# max232.net
KiCad netlist of a schematic drawn in EAGLE
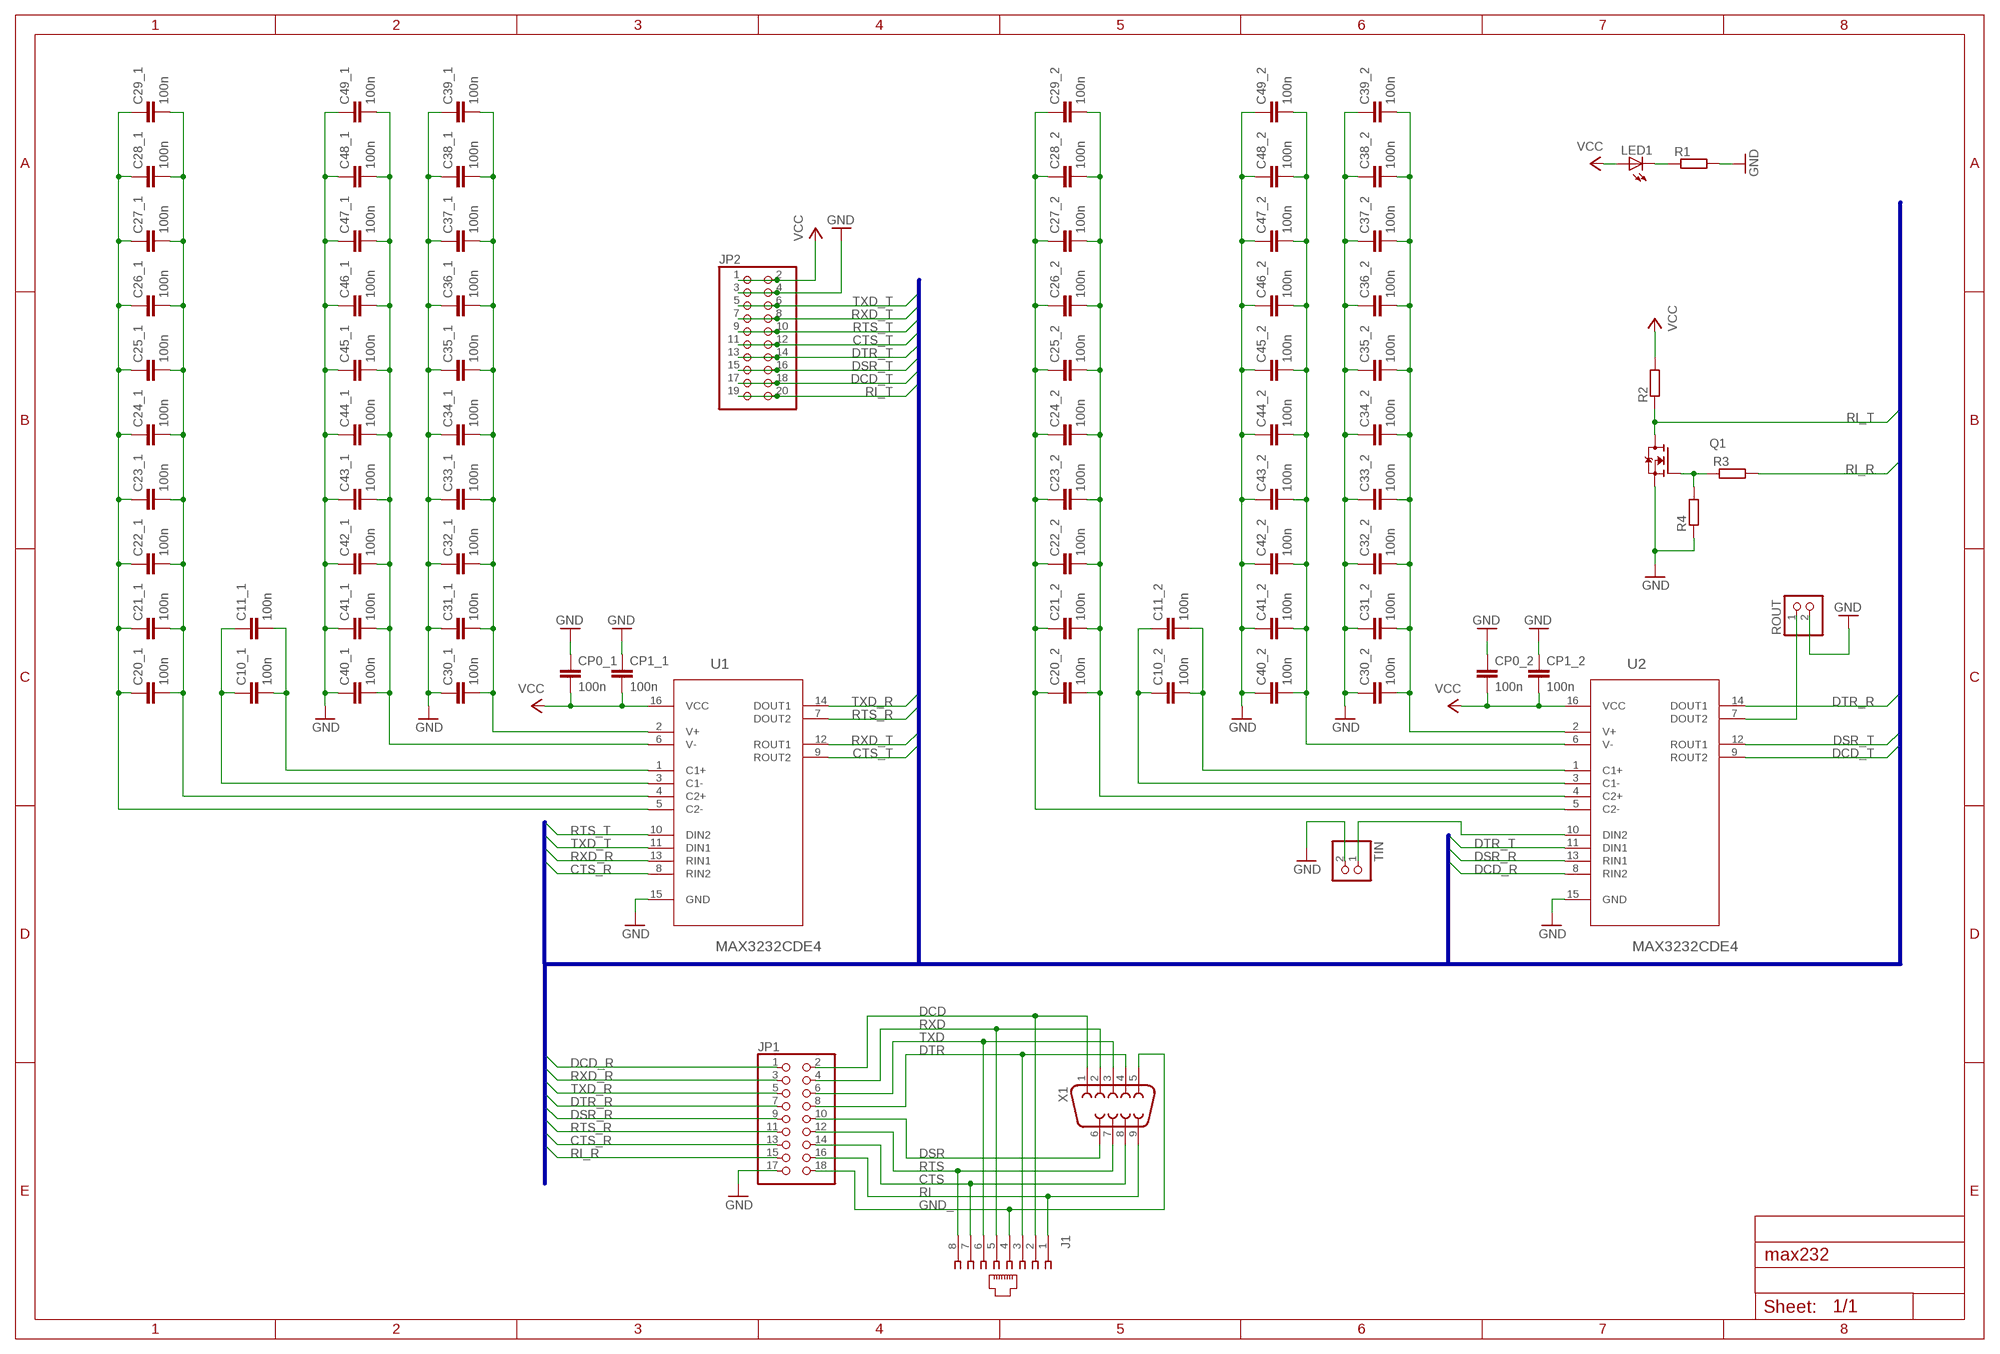
[diagram p0: schematic, sheet 1]

(export (version "E")
  (design (tool "Eeschema 10.0.6"))
  (components
    (comp (ref "C10_1")
      (value "100n")
      (footprint "eagle-import:C0402")
      (libsource (lib "eagle-import") (part "C-EUC0402"))
    )
    (comp (ref "C10_2")
      (value "100n")
      (footprint "eagle-import:C0402")
      (libsource (lib "eagle-import") (part "C-EUC0402"))
    )
    (comp (ref "C11_1")
      (value "100n")
      (footprint "eagle-import:C0402")
      (libsource (lib "eagle-import") (part "C-EUC0402"))
    )
    (comp (ref "C11_2")
      (value "100n")
      (footprint "eagle-import:C0402")
      (libsource (lib "eagle-import") (part "C-EUC0402"))
    )
    (comp (ref "C20_1")
      (value "100n")
      (footprint "eagle-import:C0402")
      (libsource (lib "eagle-import") (part "C-EUC0402"))
    )
    (comp (ref "C20_2")
      (value "100n")
      (footprint "eagle-import:C0402")
      (libsource (lib "eagle-import") (part "C-EUC0402"))
    )
    (comp (ref "C21_1")
      (value "100n")
      (footprint "eagle-import:C0402")
      (libsource (lib "eagle-import") (part "C-EUC0402"))
    )
    (comp (ref "C21_2")
      (value "100n")
      (footprint "eagle-import:C0402")
      (libsource (lib "eagle-import") (part "C-EUC0402"))
    )
    (comp (ref "C22_1")
      (value "100n")
      (footprint "eagle-import:C0402")
      (libsource (lib "eagle-import") (part "C-EUC0402"))
    )
    (comp (ref "C22_2")
      (value "100n")
      (footprint "eagle-import:C0402")
      (libsource (lib "eagle-import") (part "C-EUC0402"))
    )
    (comp (ref "C23_1")
      (value "100n")
      (footprint "eagle-import:C0402")
      (libsource (lib "eagle-import") (part "C-EUC0402"))
    )
    (comp (ref "C23_2")
      (value "100n")
      (footprint "eagle-import:C0402")
      (libsource (lib "eagle-import") (part "C-EUC0402"))
    )
    (comp (ref "C24_1")
      (value "100n")
      (footprint "eagle-import:C0402")
      (libsource (lib "eagle-import") (part "C-EUC0402"))
    )
    (comp (ref "C24_2")
      (value "100n")
      (footprint "eagle-import:C0402")
      (libsource (lib "eagle-import") (part "C-EUC0402"))
    )
    (comp (ref "C25_1")
      (value "100n")
      (footprint "eagle-import:C0402")
      (libsource (lib "eagle-import") (part "C-EUC0402"))
    )
    (comp (ref "C25_2")
      (value "100n")
      (footprint "eagle-import:C0402")
      (libsource (lib "eagle-import") (part "C-EUC0402"))
    )
    (comp (ref "C26_1")
      (value "100n")
      (footprint "eagle-import:C0402")
      (libsource (lib "eagle-import") (part "C-EUC0402"))
    )
    (comp (ref "C26_2")
      (value "100n")
      (footprint "eagle-import:C0402")
      (libsource (lib "eagle-import") (part "C-EUC0402"))
    )
    (comp (ref "C27_1")
      (value "100n")
      (footprint "eagle-import:C0402")
      (libsource (lib "eagle-import") (part "C-EUC0402"))
    )
    (comp (ref "C27_2")
      (value "100n")
      (footprint "eagle-import:C0402")
      (libsource (lib "eagle-import") (part "C-EUC0402"))
    )
    (comp (ref "C28_1")
      (value "100n")
      (footprint "eagle-import:C0402")
      (libsource (lib "eagle-import") (part "C-EUC0402"))
    )
    (comp (ref "C28_2")
      (value "100n")
      (footprint "eagle-import:C0402")
      (libsource (lib "eagle-import") (part "C-EUC0402"))
    )
    (comp (ref "C29_1")
      (value "100n")
      (footprint "eagle-import:C0402")
      (libsource (lib "eagle-import") (part "C-EUC0402"))
    )
    (comp (ref "C29_2")
      (value "100n")
      (footprint "eagle-import:C0402")
      (libsource (lib "eagle-import") (part "C-EUC0402"))
    )
    (comp (ref "C30_1")
      (value "100n")
      (footprint "eagle-import:C0402")
      (libsource (lib "eagle-import") (part "C-EUC0402"))
    )
    (comp (ref "C30_2")
      (value "100n")
      (footprint "eagle-import:C0402")
      (libsource (lib "eagle-import") (part "C-EUC0402"))
    )
    (comp (ref "C31_1")
      (value "100n")
      (footprint "eagle-import:C0402")
      (libsource (lib "eagle-import") (part "C-EUC0402"))
    )
    (comp (ref "C31_2")
      (value "100n")
      (footprint "eagle-import:C0402")
      (libsource (lib "eagle-import") (part "C-EUC0402"))
    )
    (comp (ref "C32_1")
      (value "100n")
      (footprint "eagle-import:C0402")
      (libsource (lib "eagle-import") (part "C-EUC0402"))
    )
    (comp (ref "C32_2")
      (value "100n")
      (footprint "eagle-import:C0402")
      (libsource (lib "eagle-import") (part "C-EUC0402"))
    )
    (comp (ref "C33_1")
      (value "100n")
      (footprint "eagle-import:C0402")
      (libsource (lib "eagle-import") (part "C-EUC0402"))
    )
    (comp (ref "C33_2")
      (value "100n")
      (footprint "eagle-import:C0402")
      (libsource (lib "eagle-import") (part "C-EUC0402"))
    )
    (comp (ref "C34_1")
      (value "100n")
      (footprint "eagle-import:C0402")
      (libsource (lib "eagle-import") (part "C-EUC0402"))
    )
    (comp (ref "C34_2")
      (value "100n")
      (footprint "eagle-import:C0402")
      (libsource (lib "eagle-import") (part "C-EUC0402"))
    )
    (comp (ref "C35_1")
      (value "100n")
      (footprint "eagle-import:C0402")
      (libsource (lib "eagle-import") (part "C-EUC0402"))
    )
    (comp (ref "C35_2")
      (value "100n")
      (footprint "eagle-import:C0402")
      (libsource (lib "eagle-import") (part "C-EUC0402"))
    )
    (comp (ref "C36_1")
      (value "100n")
      (footprint "eagle-import:C0402")
      (libsource (lib "eagle-import") (part "C-EUC0402"))
    )
    (comp (ref "C36_2")
      (value "100n")
      (footprint "eagle-import:C0402")
      (libsource (lib "eagle-import") (part "C-EUC0402"))
    )
    (comp (ref "C37_1")
      (value "100n")
      (footprint "eagle-import:C0402")
      (libsource (lib "eagle-import") (part "C-EUC0402"))
    )
    (comp (ref "C37_2")
      (value "100n")
      (footprint "eagle-import:C0402")
      (libsource (lib "eagle-import") (part "C-EUC0402"))
    )
    (comp (ref "C38_1")
      (value "100n")
      (footprint "eagle-import:C0402")
      (libsource (lib "eagle-import") (part "C-EUC0402"))
    )
    (comp (ref "C38_2")
      (value "100n")
      (footprint "eagle-import:C0402")
      (libsource (lib "eagle-import") (part "C-EUC0402"))
    )
    (comp (ref "C39_1")
      (value "100n")
      (footprint "eagle-import:C0402")
      (libsource (lib "eagle-import") (part "C-EUC0402"))
    )
    (comp (ref "C39_2")
      (value "100n")
      (footprint "eagle-import:C0402")
      (libsource (lib "eagle-import") (part "C-EUC0402"))
    )
    (comp (ref "C40_1")
      (value "100n")
      (footprint "eagle-import:C0402")
      (libsource (lib "eagle-import") (part "C-EUC0402"))
    )
    (comp (ref "C40_2")
      (value "100n")
      (footprint "eagle-import:C0402")
      (libsource (lib "eagle-import") (part "C-EUC0402"))
    )
    (comp (ref "C41_1")
      (value "100n")
      (footprint "eagle-import:C0402")
      (libsource (lib "eagle-import") (part "C-EUC0402"))
    )
    (comp (ref "C41_2")
      (value "100n")
      (footprint "eagle-import:C0402")
      (libsource (lib "eagle-import") (part "C-EUC0402"))
    )
    (comp (ref "C42_1")
      (value "100n")
      (footprint "eagle-import:C0402")
      (libsource (lib "eagle-import") (part "C-EUC0402"))
    )
    (comp (ref "C42_2")
      (value "100n")
      (footprint "eagle-import:C0402")
      (libsource (lib "eagle-import") (part "C-EUC0402"))
    )
    (comp (ref "C43_1")
      (value "100n")
      (footprint "eagle-import:C0402")
      (libsource (lib "eagle-import") (part "C-EUC0402"))
    )
    (comp (ref "C43_2")
      (value "100n")
      (footprint "eagle-import:C0402")
      (libsource (lib "eagle-import") (part "C-EUC0402"))
    )
    (comp (ref "C44_1")
      (value "100n")
      (footprint "eagle-import:C0402")
      (libsource (lib "eagle-import") (part "C-EUC0402"))
    )
    (comp (ref "C44_2")
      (value "100n")
      (footprint "eagle-import:C0402")
      (libsource (lib "eagle-import") (part "C-EUC0402"))
    )
    (comp (ref "C45_1")
      (value "100n")
      (footprint "eagle-import:C0402")
      (libsource (lib "eagle-import") (part "C-EUC0402"))
    )
    (comp (ref "C45_2")
      (value "100n")
      (footprint "eagle-import:C0402")
      (libsource (lib "eagle-import") (part "C-EUC0402"))
    )
    (comp (ref "C46_1")
      (value "100n")
      (footprint "eagle-import:C0402")
      (libsource (lib "eagle-import") (part "C-EUC0402"))
    )
    (comp (ref "C46_2")
      (value "100n")
      (footprint "eagle-import:C0402")
      (libsource (lib "eagle-import") (part "C-EUC0402"))
    )
    (comp (ref "C47_1")
      (value "100n")
      (footprint "eagle-import:C0402")
      (libsource (lib "eagle-import") (part "C-EUC0402"))
    )
    (comp (ref "C47_2")
      (value "100n")
      (footprint "eagle-import:C0402")
      (libsource (lib "eagle-import") (part "C-EUC0402"))
    )
    (comp (ref "C48_1")
      (value "100n")
      (footprint "eagle-import:C0402")
      (libsource (lib "eagle-import") (part "C-EUC0402"))
    )
    (comp (ref "C48_2")
      (value "100n")
      (footprint "eagle-import:C0402")
      (libsource (lib "eagle-import") (part "C-EUC0402"))
    )
    (comp (ref "C49_1")
      (value "100n")
      (footprint "eagle-import:C0402")
      (libsource (lib "eagle-import") (part "C-EUC0402"))
    )
    (comp (ref "C49_2")
      (value "100n")
      (footprint "eagle-import:C0402")
      (libsource (lib "eagle-import") (part "C-EUC0402"))
    )
    (comp (ref "CP0_1")
      (value "100n")
      (footprint "eagle-import:C0402")
      (libsource (lib "eagle-import") (part "C-EUC0402"))
    )
    (comp (ref "CP0_2")
      (value "100n")
      (footprint "eagle-import:C0402")
      (libsource (lib "eagle-import") (part "C-EUC0402"))
    )
    (comp (ref "CP1_1")
      (value "100n")
      (footprint "eagle-import:C0402")
      (libsource (lib "eagle-import") (part "C-EUC0402"))
    )
    (comp (ref "CP1_2")
      (value "100n")
      (footprint "eagle-import:C0402")
      (libsource (lib "eagle-import") (part "C-EUC0402"))
    )
    (comp (ref "J1")
      (value "215877-4")
      (footprint "eagle-import:215877-4")
      (libsource (lib "eagle-import") (part "215877-4"))
    )
    (comp (ref "JP1")
      (value "PINHD-2X9")
      (footprint "eagle-import:2X09")
      (libsource (lib "eagle-import") (part "PINHD-2X9"))
    )
    (comp (ref "JP2")
      (value "PINHD-2X10/90")
      (footprint "eagle-import:2X10_90")
      (libsource (lib "eagle-import") (part "PINHD-2X10/90"))
    )
    (comp (ref "LED1")
      (value "LEDCHIP-LED0603")
      (footprint "eagle-import:CHIP-LED0603")
      (libsource (lib "eagle-import") (part "LEDCHIP-LED0603"))
    )
    (comp (ref "Q1")
      (value "N-MOSFET-SOT23-GSD")
      (footprint "eagle-import:SOT23")
      (libsource (lib "eagle-import") (part "N-MOSFET-SOT23-GSD"))
    )
    (comp (ref "R1")
      (value "R-EU_R0603")
      (footprint "eagle-import:R0603")
      (libsource (lib "eagle-import") (part "R-EU_R0603"))
    )
    (comp (ref "R2")
      (value "R-EU_R0603")
      (footprint "eagle-import:R0603")
      (libsource (lib "eagle-import") (part "R-EU_R0603"))
    )
    (comp (ref "R3")
      (value "R-EU_R0603")
      (footprint "eagle-import:R0603")
      (libsource (lib "eagle-import") (part "R-EU_R0603"))
    )
    (comp (ref "R4")
      (value "R-EU_R0603")
      (footprint "eagle-import:R0603")
      (libsource (lib "eagle-import") (part "R-EU_R0603"))
    )
    (comp (ref "ROUT")
      (value "PINHD-1X2")
      (footprint "eagle-import:1X02")
      (libsource (lib "eagle-import") (part "PINHD-1X2"))
    )
    (comp (ref "TIN")
      (value "PINHD-1X2")
      (footprint "eagle-import:1X02")
      (libsource (lib "eagle-import") (part "PINHD-1X2"))
    )
    (comp (ref "U1")
      (value "MAX3232CDE4")
      (footprint "eagle-import:SOIC127P600X175-16N")
      (libsource (lib "eagle-import") (part "MAX3232CDE4"))
    )
    (comp (ref "U2")
      (value "MAX3232CDE4")
      (footprint "eagle-import:SOIC127P600X175-16N")
      (libsource (lib "eagle-import") (part "MAX3232CDE4"))
    )
    (comp (ref "X1")
      (value "F09HP")
      (footprint "eagle-import:F09HP")
      (libsource (lib "eagle-import") (part "F09HP"))
    )
  )
  (nets
    (net (code "1") (name "/CTS") (class "Default")
      (node (ref "J1") (pin "7") (pinfunction "7_7") (pintype "passive"))
      (node (ref "JP1") (pin "14") (pinfunction "14_14") (pintype "passive"))
      (node (ref "X1") (pin "8") (pinfunction "8_8") (pintype "passive"))
    )
    (net (code "2") (name "/CTS_R") (class "Default")
      (node (ref "JP1") (pin "13") (pinfunction "13_13") (pintype "passive"))
      (node (ref "U1") (pin "8") (pinfunction "RIN2_8") (pintype "input"))
    )
    (net (code "3") (name "/CTS_T") (class "Default")
      (node (ref "JP2") (pin "11") (pinfunction "11_11") (pintype "passive"))
      (node (ref "JP2") (pin "12") (pinfunction "12_12") (pintype "passive"))
      (node (ref "U1") (pin "9") (pinfunction "ROUT2_9") (pintype "output"))
    )
    (net (code "4") (name "/DCD") (class "Default")
      (node (ref "J1") (pin "2") (pinfunction "2_2") (pintype "passive"))
      (node (ref "JP1") (pin "2") (pinfunction "2_2") (pintype "passive"))
      (node (ref "X1") (pin "1") (pinfunction "1_1") (pintype "passive"))
    )
    (net (code "5") (name "/DCD_R") (class "Default")
      (node (ref "JP1") (pin "1") (pinfunction "1_1") (pintype "passive"))
      (node (ref "U2") (pin "8") (pinfunction "RIN2_8") (pintype "input"))
    )
    (net (code "6") (name "/DCD_T") (class "Default")
      (node (ref "JP2") (pin "17") (pinfunction "17_17") (pintype "passive"))
      (node (ref "JP2") (pin "18") (pinfunction "18_18") (pintype "passive"))
      (node (ref "U2") (pin "9") (pinfunction "ROUT2_9") (pintype "output"))
    )
    (net (code "7") (name "/DSR") (class "Default")
      (node (ref "JP1") (pin "10") (pinfunction "10_10") (pintype "passive"))
      (node (ref "X1") (pin "6") (pinfunction "6_6") (pintype "passive"))
    )
    (net (code "8") (name "/DSR_R") (class "Default")
      (node (ref "JP1") (pin "9") (pinfunction "9_9") (pintype "passive"))
      (node (ref "U2") (pin "13") (pinfunction "RIN1_13") (pintype "input"))
    )
    (net (code "9") (name "/DSR_T") (class "Default")
      (node (ref "JP2") (pin "15") (pinfunction "15_15") (pintype "passive"))
      (node (ref "JP2") (pin "16") (pinfunction "16_16") (pintype "passive"))
      (node (ref "U2") (pin "12") (pinfunction "ROUT1_12") (pintype "output"))
    )
    (net (code "10") (name "/DTR") (class "Default")
      (node (ref "J1") (pin "3") (pinfunction "3_3") (pintype "passive"))
      (node (ref "JP1") (pin "8") (pinfunction "8_8") (pintype "passive"))
      (node (ref "X1") (pin "4") (pinfunction "4_4") (pintype "passive"))
    )
    (net (code "11") (name "/DTR_R") (class "Default")
      (node (ref "JP1") (pin "7") (pinfunction "7_7") (pintype "passive"))
      (node (ref "U2") (pin "14") (pinfunction "DOUT1_14") (pintype "output"))
    )
    (net (code "12") (name "/DTR_T") (class "Default")
      (node (ref "JP2") (pin "13") (pinfunction "13_13") (pintype "passive"))
      (node (ref "JP2") (pin "14") (pinfunction "14_14") (pintype "passive"))
      (node (ref "U2") (pin "11") (pinfunction "DIN1_11") (pintype "input"))
    )
    (net (code "13") (name "/GND_") (class "Default")
      (node (ref "J1") (pin "4") (pinfunction "4_4") (pintype "passive"))
      (node (ref "JP1") (pin "18") (pinfunction "18_18") (pintype "passive"))
      (node (ref "X1") (pin "5") (pinfunction "5_5") (pintype "passive"))
    )
    (net (code "14") (name "/RI") (class "Default")
      (node (ref "J1") (pin "1") (pinfunction "1_1") (pintype "passive"))
      (node (ref "JP1") (pin "16") (pinfunction "16_16") (pintype "passive"))
      (node (ref "X1") (pin "9") (pinfunction "9_9") (pintype "passive"))
    )
    (net (code "15") (name "/RI_R") (class "Default")
      (node (ref "JP1") (pin "15") (pinfunction "15_15") (pintype "passive"))
      (node (ref "R3") (pin "2") (pinfunction "2_2") (pintype "passive"))
    )
    (net (code "16") (name "/RI_T") (class "Default")
      (node (ref "JP2") (pin "19") (pinfunction "19_19") (pintype "passive"))
      (node (ref "JP2") (pin "20") (pinfunction "20_20") (pintype "passive"))
      (node (ref "Q1") (pin "3") (pinfunction "D_3") (pintype "passive"))
      (node (ref "R2") (pin "1") (pinfunction "1_1") (pintype "passive"))
    )
    (net (code "17") (name "/RTS") (class "Default")
      (node (ref "J1") (pin "8") (pinfunction "8_8") (pintype "passive"))
      (node (ref "JP1") (pin "12") (pinfunction "12_12") (pintype "passive"))
      (node (ref "X1") (pin "7") (pinfunction "7_7") (pintype "passive"))
    )
    (net (code "18") (name "/RTS_R") (class "Default")
      (node (ref "JP1") (pin "11") (pinfunction "11_11") (pintype "passive"))
      (node (ref "U1") (pin "7") (pinfunction "DOUT2_7") (pintype "output"))
    )
    (net (code "19") (name "/RTS_T") (class "Default")
      (node (ref "JP2") (pin "10") (pinfunction "10_10") (pintype "passive"))
      (node (ref "JP2") (pin "9") (pinfunction "9_9") (pintype "passive"))
      (node (ref "U1") (pin "10") (pinfunction "DIN2_10") (pintype "input"))
    )
    (net (code "20") (name "/RXD") (class "Default")
      (node (ref "J1") (pin "5") (pinfunction "5_5") (pintype "passive"))
      (node (ref "JP1") (pin "4") (pinfunction "4_4") (pintype "passive"))
      (node (ref "X1") (pin "2") (pinfunction "2_2") (pintype "passive"))
    )
    (net (code "21") (name "/RXD_R") (class "Default")
      (node (ref "JP1") (pin "3") (pinfunction "3_3") (pintype "passive"))
      (node (ref "U1") (pin "13") (pinfunction "RIN1_13") (pintype "input"))
    )
    (net (code "22") (name "/RXD_T") (class "Default")
      (node (ref "JP2") (pin "7") (pinfunction "7_7") (pintype "passive"))
      (node (ref "JP2") (pin "8") (pinfunction "8_8") (pintype "passive"))
      (node (ref "U1") (pin "12") (pinfunction "ROUT1_12") (pintype "output"))
    )
    (net (code "23") (name "/TXD") (class "Default")
      (node (ref "J1") (pin "6") (pinfunction "6_6") (pintype "passive"))
      (node (ref "JP1") (pin "6") (pinfunction "6_6") (pintype "passive"))
      (node (ref "X1") (pin "3") (pinfunction "3_3") (pintype "passive"))
    )
    (net (code "24") (name "/TXD_R") (class "Default")
      (node (ref "JP1") (pin "5") (pinfunction "5_5") (pintype "passive"))
      (node (ref "U1") (pin "14") (pinfunction "DOUT1_14") (pintype "output"))
    )
    (net (code "25") (name "/TXD_T") (class "Default")
      (node (ref "JP2") (pin "5") (pinfunction "5_5") (pintype "passive"))
      (node (ref "JP2") (pin "6") (pinfunction "6_6") (pintype "passive"))
      (node (ref "U1") (pin "11") (pinfunction "DIN1_11") (pintype "input"))
    )
    (net (code "26") (name "GND") (class "Default")
      (node (ref "C30_1") (pin "1") (pinfunction "1_1") (pintype "passive"))
      (node (ref "C30_2") (pin "1") (pinfunction "1_1") (pintype "passive"))
      (node (ref "C31_1") (pin "1") (pinfunction "1_1") (pintype "passive"))
      (node (ref "C31_2") (pin "1") (pinfunction "1_1") (pintype "passive"))
      (node (ref "C32_1") (pin "1") (pinfunction "1_1") (pintype "passive"))
      (node (ref "C32_2") (pin "1") (pinfunction "1_1") (pintype "passive"))
      (node (ref "C33_1") (pin "1") (pinfunction "1_1") (pintype "passive"))
      (node (ref "C33_2") (pin "1") (pinfunction "1_1") (pintype "passive"))
      (node (ref "C34_1") (pin "1") (pinfunction "1_1") (pintype "passive"))
      (node (ref "C34_2") (pin "1") (pinfunction "1_1") (pintype "passive"))
      (node (ref "C35_1") (pin "1") (pinfunction "1_1") (pintype "passive"))
      (node (ref "C35_2") (pin "1") (pinfunction "1_1") (pintype "passive"))
      (node (ref "C36_1") (pin "1") (pinfunction "1_1") (pintype "passive"))
      (node (ref "C36_2") (pin "1") (pinfunction "1_1") (pintype "passive"))
      (node (ref "C37_1") (pin "1") (pinfunction "1_1") (pintype "passive"))
      (node (ref "C37_2") (pin "1") (pinfunction "1_1") (pintype "passive"))
      (node (ref "C38_1") (pin "1") (pinfunction "1_1") (pintype "passive"))
      (node (ref "C38_2") (pin "1") (pinfunction "1_1") (pintype "passive"))
      (node (ref "C39_1") (pin "1") (pinfunction "1_1") (pintype "passive"))
      (node (ref "C39_2") (pin "1") (pinfunction "1_1") (pintype "passive"))
      (node (ref "C40_1") (pin "1") (pinfunction "1_1") (pintype "passive"))
      (node (ref "C40_2") (pin "1") (pinfunction "1_1") (pintype "passive"))
      (node (ref "C41_1") (pin "1") (pinfunction "1_1") (pintype "passive"))
      (node (ref "C41_2") (pin "1") (pinfunction "1_1") (pintype "passive"))
      (node (ref "C42_1") (pin "1") (pinfunction "1_1") (pintype "passive"))
      (node (ref "C42_2") (pin "1") (pinfunction "1_1") (pintype "passive"))
      (node (ref "C43_1") (pin "1") (pinfunction "1_1") (pintype "passive"))
      (node (ref "C43_2") (pin "1") (pinfunction "1_1") (pintype "passive"))
      (node (ref "C44_1") (pin "1") (pinfunction "1_1") (pintype "passive"))
      (node (ref "C44_2") (pin "1") (pinfunction "1_1") (pintype "passive"))
      (node (ref "C45_1") (pin "1") (pinfunction "1_1") (pintype "passive"))
      (node (ref "C45_2") (pin "1") (pinfunction "1_1") (pintype "passive"))
      (node (ref "C46_1") (pin "1") (pinfunction "1_1") (pintype "passive"))
      (node (ref "C46_2") (pin "1") (pinfunction "1_1") (pintype "passive"))
      (node (ref "C47_1") (pin "1") (pinfunction "1_1") (pintype "passive"))
      (node (ref "C47_2") (pin "1") (pinfunction "1_1") (pintype "passive"))
      (node (ref "C48_1") (pin "1") (pinfunction "1_1") (pintype "passive"))
      (node (ref "C48_2") (pin "1") (pinfunction "1_1") (pintype "passive"))
      (node (ref "C49_1") (pin "1") (pinfunction "1_1") (pintype "passive"))
      (node (ref "C49_2") (pin "1") (pinfunction "1_1") (pintype "passive"))
      (node (ref "CP0_1") (pin "1") (pinfunction "1_1") (pintype "passive"))
      (node (ref "CP0_2") (pin "1") (pinfunction "1_1") (pintype "passive"))
      (node (ref "CP1_1") (pin "1") (pinfunction "1_1") (pintype "passive"))
      (node (ref "CP1_2") (pin "1") (pinfunction "1_1") (pintype "passive"))
      (node (ref "JP1") (pin "17") (pinfunction "17_17") (pintype "passive"))
      (node (ref "JP2") (pin "3") (pinfunction "3_3") (pintype "passive"))
      (node (ref "JP2") (pin "4") (pinfunction "4_4") (pintype "passive"))
      (node (ref "Q1") (pin "2") (pinfunction "S_2") (pintype "passive"))
      (node (ref "R1") (pin "2") (pinfunction "2_2") (pintype "passive"))
      (node (ref "R4") (pin "1") (pinfunction "1_1") (pintype "passive"))
      (node (ref "ROUT") (pin "2") (pinfunction "2_2") (pintype "passive"))
      (node (ref "TIN") (pin "2") (pinfunction "2_2") (pintype "passive"))
      (node (ref "U1") (pin "15") (pinfunction "GND_15") (pintype "passive"))
      (node (ref "U2") (pin "15") (pinfunction "GND_15") (pintype "passive"))
    )
    (net (code "27") (name "Net-(LED1-PadC)") (class "Default")
      (node (ref "LED1") (pin "C") (pinfunction "C_C") (pintype "passive"))
      (node (ref "R1") (pin "1") (pinfunction "1_1") (pintype "passive"))
    )
    (net (code "28") (name "Net-(Q1-G)") (class "Default")
      (node (ref "Q1") (pin "1") (pinfunction "G_1") (pintype "passive"))
      (node (ref "R3") (pin "1") (pinfunction "1_1") (pintype "passive"))
      (node (ref "R4") (pin "2") (pinfunction "2_2") (pintype "passive"))
    )
    (net (code "29") (name "Net-(U1-C1+)") (class "Default")
      (node (ref "C10_1") (pin "2") (pinfunction "2_2") (pintype "passive"))
      (node (ref "C11_1") (pin "2") (pinfunction "2_2") (pintype "passive"))
      (node (ref "U1") (pin "1") (pinfunction "C1+_1") (pintype "passive"))
    )
    (net (code "30") (name "Net-(U1-C1-)") (class "Default")
      (node (ref "C10_1") (pin "1") (pinfunction "1_1") (pintype "passive"))
      (node (ref "C11_1") (pin "1") (pinfunction "1_1") (pintype "passive"))
      (node (ref "U1") (pin "3") (pinfunction "C1-_3") (pintype "passive"))
    )
    (net (code "31") (name "Net-(U1-C2+)") (class "Default")
      (node (ref "C20_1") (pin "2") (pinfunction "2_2") (pintype "passive"))
      (node (ref "C21_1") (pin "2") (pinfunction "2_2") (pintype "passive"))
      (node (ref "C22_1") (pin "2") (pinfunction "2_2") (pintype "passive"))
      (node (ref "C23_1") (pin "2") (pinfunction "2_2") (pintype "passive"))
      (node (ref "C24_1") (pin "2") (pinfunction "2_2") (pintype "passive"))
      (node (ref "C25_1") (pin "2") (pinfunction "2_2") (pintype "passive"))
      (node (ref "C26_1") (pin "2") (pinfunction "2_2") (pintype "passive"))
      (node (ref "C27_1") (pin "2") (pinfunction "2_2") (pintype "passive"))
      (node (ref "C28_1") (pin "2") (pinfunction "2_2") (pintype "passive"))
      (node (ref "C29_1") (pin "2") (pinfunction "2_2") (pintype "passive"))
      (node (ref "U1") (pin "4") (pinfunction "C2+_4") (pintype "passive"))
    )
    (net (code "32") (name "Net-(U1-C2-)") (class "Default")
      (node (ref "C20_1") (pin "1") (pinfunction "1_1") (pintype "passive"))
      (node (ref "C21_1") (pin "1") (pinfunction "1_1") (pintype "passive"))
      (node (ref "C22_1") (pin "1") (pinfunction "1_1") (pintype "passive"))
      (node (ref "C23_1") (pin "1") (pinfunction "1_1") (pintype "passive"))
      (node (ref "C24_1") (pin "1") (pinfunction "1_1") (pintype "passive"))
      (node (ref "C25_1") (pin "1") (pinfunction "1_1") (pintype "passive"))
      (node (ref "C26_1") (pin "1") (pinfunction "1_1") (pintype "passive"))
      (node (ref "C27_1") (pin "1") (pinfunction "1_1") (pintype "passive"))
      (node (ref "C28_1") (pin "1") (pinfunction "1_1") (pintype "passive"))
      (node (ref "C29_1") (pin "1") (pinfunction "1_1") (pintype "passive"))
      (node (ref "U1") (pin "5") (pinfunction "C2-_5") (pintype "passive"))
    )
    (net (code "33") (name "Net-(U1-V+)") (class "Default")
      (node (ref "C30_1") (pin "2") (pinfunction "2_2") (pintype "passive"))
      (node (ref "C31_1") (pin "2") (pinfunction "2_2") (pintype "passive"))
      (node (ref "C32_1") (pin "2") (pinfunction "2_2") (pintype "passive"))
      (node (ref "C33_1") (pin "2") (pinfunction "2_2") (pintype "passive"))
      (node (ref "C34_1") (pin "2") (pinfunction "2_2") (pintype "passive"))
      (node (ref "C35_1") (pin "2") (pinfunction "2_2") (pintype "passive"))
      (node (ref "C36_1") (pin "2") (pinfunction "2_2") (pintype "passive"))
      (node (ref "C37_1") (pin "2") (pinfunction "2_2") (pintype "passive"))
      (node (ref "C38_1") (pin "2") (pinfunction "2_2") (pintype "passive"))
      (node (ref "C39_1") (pin "2") (pinfunction "2_2") (pintype "passive"))
      (node (ref "U1") (pin "2") (pinfunction "V+_2") (pintype "input"))
    )
    (net (code "34") (name "Net-(U1-V-)") (class "Default")
      (node (ref "C40_1") (pin "2") (pinfunction "2_2") (pintype "passive"))
      (node (ref "C41_1") (pin "2") (pinfunction "2_2") (pintype "passive"))
      (node (ref "C42_1") (pin "2") (pinfunction "2_2") (pintype "passive"))
      (node (ref "C43_1") (pin "2") (pinfunction "2_2") (pintype "passive"))
      (node (ref "C44_1") (pin "2") (pinfunction "2_2") (pintype "passive"))
      (node (ref "C45_1") (pin "2") (pinfunction "2_2") (pintype "passive"))
      (node (ref "C46_1") (pin "2") (pinfunction "2_2") (pintype "passive"))
      (node (ref "C47_1") (pin "2") (pinfunction "2_2") (pintype "passive"))
      (node (ref "C48_1") (pin "2") (pinfunction "2_2") (pintype "passive"))
      (node (ref "C49_1") (pin "2") (pinfunction "2_2") (pintype "passive"))
      (node (ref "U1") (pin "6") (pinfunction "V-_6") (pintype "input"))
    )
    (net (code "35") (name "Net-(U2-C1+)") (class "Default")
      (node (ref "C10_2") (pin "2") (pinfunction "2_2") (pintype "passive"))
      (node (ref "C11_2") (pin "2") (pinfunction "2_2") (pintype "passive"))
      (node (ref "U2") (pin "1") (pinfunction "C1+_1") (pintype "passive"))
    )
    (net (code "36") (name "Net-(U2-C1-)") (class "Default")
      (node (ref "C10_2") (pin "1") (pinfunction "1_1") (pintype "passive"))
      (node (ref "C11_2") (pin "1") (pinfunction "1_1") (pintype "passive"))
      (node (ref "U2") (pin "3") (pinfunction "C1-_3") (pintype "passive"))
    )
    (net (code "37") (name "Net-(U2-C2+)") (class "Default")
      (node (ref "C20_2") (pin "2") (pinfunction "2_2") (pintype "passive"))
      (node (ref "C21_2") (pin "2") (pinfunction "2_2") (pintype "passive"))
      (node (ref "C22_2") (pin "2") (pinfunction "2_2") (pintype "passive"))
      (node (ref "C23_2") (pin "2") (pinfunction "2_2") (pintype "passive"))
      (node (ref "C24_2") (pin "2") (pinfunction "2_2") (pintype "passive"))
      (node (ref "C25_2") (pin "2") (pinfunction "2_2") (pintype "passive"))
      (node (ref "C26_2") (pin "2") (pinfunction "2_2") (pintype "passive"))
      (node (ref "C27_2") (pin "2") (pinfunction "2_2") (pintype "passive"))
      (node (ref "C28_2") (pin "2") (pinfunction "2_2") (pintype "passive"))
      (node (ref "C29_2") (pin "2") (pinfunction "2_2") (pintype "passive"))
      (node (ref "U2") (pin "4") (pinfunction "C2+_4") (pintype "passive"))
    )
    (net (code "38") (name "Net-(U2-C2-)") (class "Default")
      (node (ref "C20_2") (pin "1") (pinfunction "1_1") (pintype "passive"))
      (node (ref "C21_2") (pin "1") (pinfunction "1_1") (pintype "passive"))
      (node (ref "C22_2") (pin "1") (pinfunction "1_1") (pintype "passive"))
      (node (ref "C23_2") (pin "1") (pinfunction "1_1") (pintype "passive"))
      (node (ref "C24_2") (pin "1") (pinfunction "1_1") (pintype "passive"))
      (node (ref "C25_2") (pin "1") (pinfunction "1_1") (pintype "passive"))
      (node (ref "C26_2") (pin "1") (pinfunction "1_1") (pintype "passive"))
      (node (ref "C27_2") (pin "1") (pinfunction "1_1") (pintype "passive"))
      (node (ref "C28_2") (pin "1") (pinfunction "1_1") (pintype "passive"))
      (node (ref "C29_2") (pin "1") (pinfunction "1_1") (pintype "passive"))
      (node (ref "U2") (pin "5") (pinfunction "C2-_5") (pintype "passive"))
    )
    (net (code "39") (name "Net-(U2-DIN2)") (class "Default")
      (node (ref "TIN") (pin "1") (pinfunction "1_1") (pintype "passive"))
      (node (ref "U2") (pin "10") (pinfunction "DIN2_10") (pintype "input"))
    )
    (net (code "40") (name "Net-(U2-DOUT2)") (class "Default")
      (node (ref "ROUT") (pin "1") (pinfunction "1_1") (pintype "passive"))
      (node (ref "U2") (pin "7") (pinfunction "DOUT2_7") (pintype "output"))
    )
    (net (code "41") (name "Net-(U2-V+)") (class "Default")
      (node (ref "C30_2") (pin "2") (pinfunction "2_2") (pintype "passive"))
      (node (ref "C31_2") (pin "2") (pinfunction "2_2") (pintype "passive"))
      (node (ref "C32_2") (pin "2") (pinfunction "2_2") (pintype "passive"))
      (node (ref "C33_2") (pin "2") (pinfunction "2_2") (pintype "passive"))
      (node (ref "C34_2") (pin "2") (pinfunction "2_2") (pintype "passive"))
      (node (ref "C35_2") (pin "2") (pinfunction "2_2") (pintype "passive"))
      (node (ref "C36_2") (pin "2") (pinfunction "2_2") (pintype "passive"))
      (node (ref "C37_2") (pin "2") (pinfunction "2_2") (pintype "passive"))
      (node (ref "C38_2") (pin "2") (pinfunction "2_2") (pintype "passive"))
      (node (ref "C39_2") (pin "2") (pinfunction "2_2") (pintype "passive"))
      (node (ref "U2") (pin "2") (pinfunction "V+_2") (pintype "input"))
    )
    (net (code "42") (name "Net-(U2-V-)") (class "Default")
      (node (ref "C40_2") (pin "2") (pinfunction "2_2") (pintype "passive"))
      (node (ref "C41_2") (pin "2") (pinfunction "2_2") (pintype "passive"))
      (node (ref "C42_2") (pin "2") (pinfunction "2_2") (pintype "passive"))
      (node (ref "C43_2") (pin "2") (pinfunction "2_2") (pintype "passive"))
      (node (ref "C44_2") (pin "2") (pinfunction "2_2") (pintype "passive"))
      (node (ref "C45_2") (pin "2") (pinfunction "2_2") (pintype "passive"))
      (node (ref "C46_2") (pin "2") (pinfunction "2_2") (pintype "passive"))
      (node (ref "C47_2") (pin "2") (pinfunction "2_2") (pintype "passive"))
      (node (ref "C48_2") (pin "2") (pinfunction "2_2") (pintype "passive"))
      (node (ref "C49_2") (pin "2") (pinfunction "2_2") (pintype "passive"))
      (node (ref "U2") (pin "6") (pinfunction "V-_6") (pintype "input"))
    )
    (net (code "43") (name "VCC") (class "Default")
      (node (ref "CP0_1") (pin "2") (pinfunction "2_2") (pintype "passive"))
      (node (ref "CP0_2") (pin "2") (pinfunction "2_2") (pintype "passive"))
      (node (ref "CP1_1") (pin "2") (pinfunction "2_2") (pintype "passive"))
      (node (ref "CP1_2") (pin "2") (pinfunction "2_2") (pintype "passive"))
      (node (ref "JP2") (pin "1") (pinfunction "1_1") (pintype "passive"))
      (node (ref "JP2") (pin "2") (pinfunction "2_2") (pintype "passive"))
      (node (ref "LED1") (pin "A") (pinfunction "A_A") (pintype "passive"))
      (node (ref "R2") (pin "2") (pinfunction "2_2") (pintype "passive"))
      (node (ref "U1") (pin "16") (pinfunction "VCC_16") (pintype "power_in"))
      (node (ref "U2") (pin "16") (pinfunction "VCC_16") (pintype "power_in"))
    )
  )
)
